# TeensyPedal.net
KiCad netlist of a schematic drawn in EAGLE
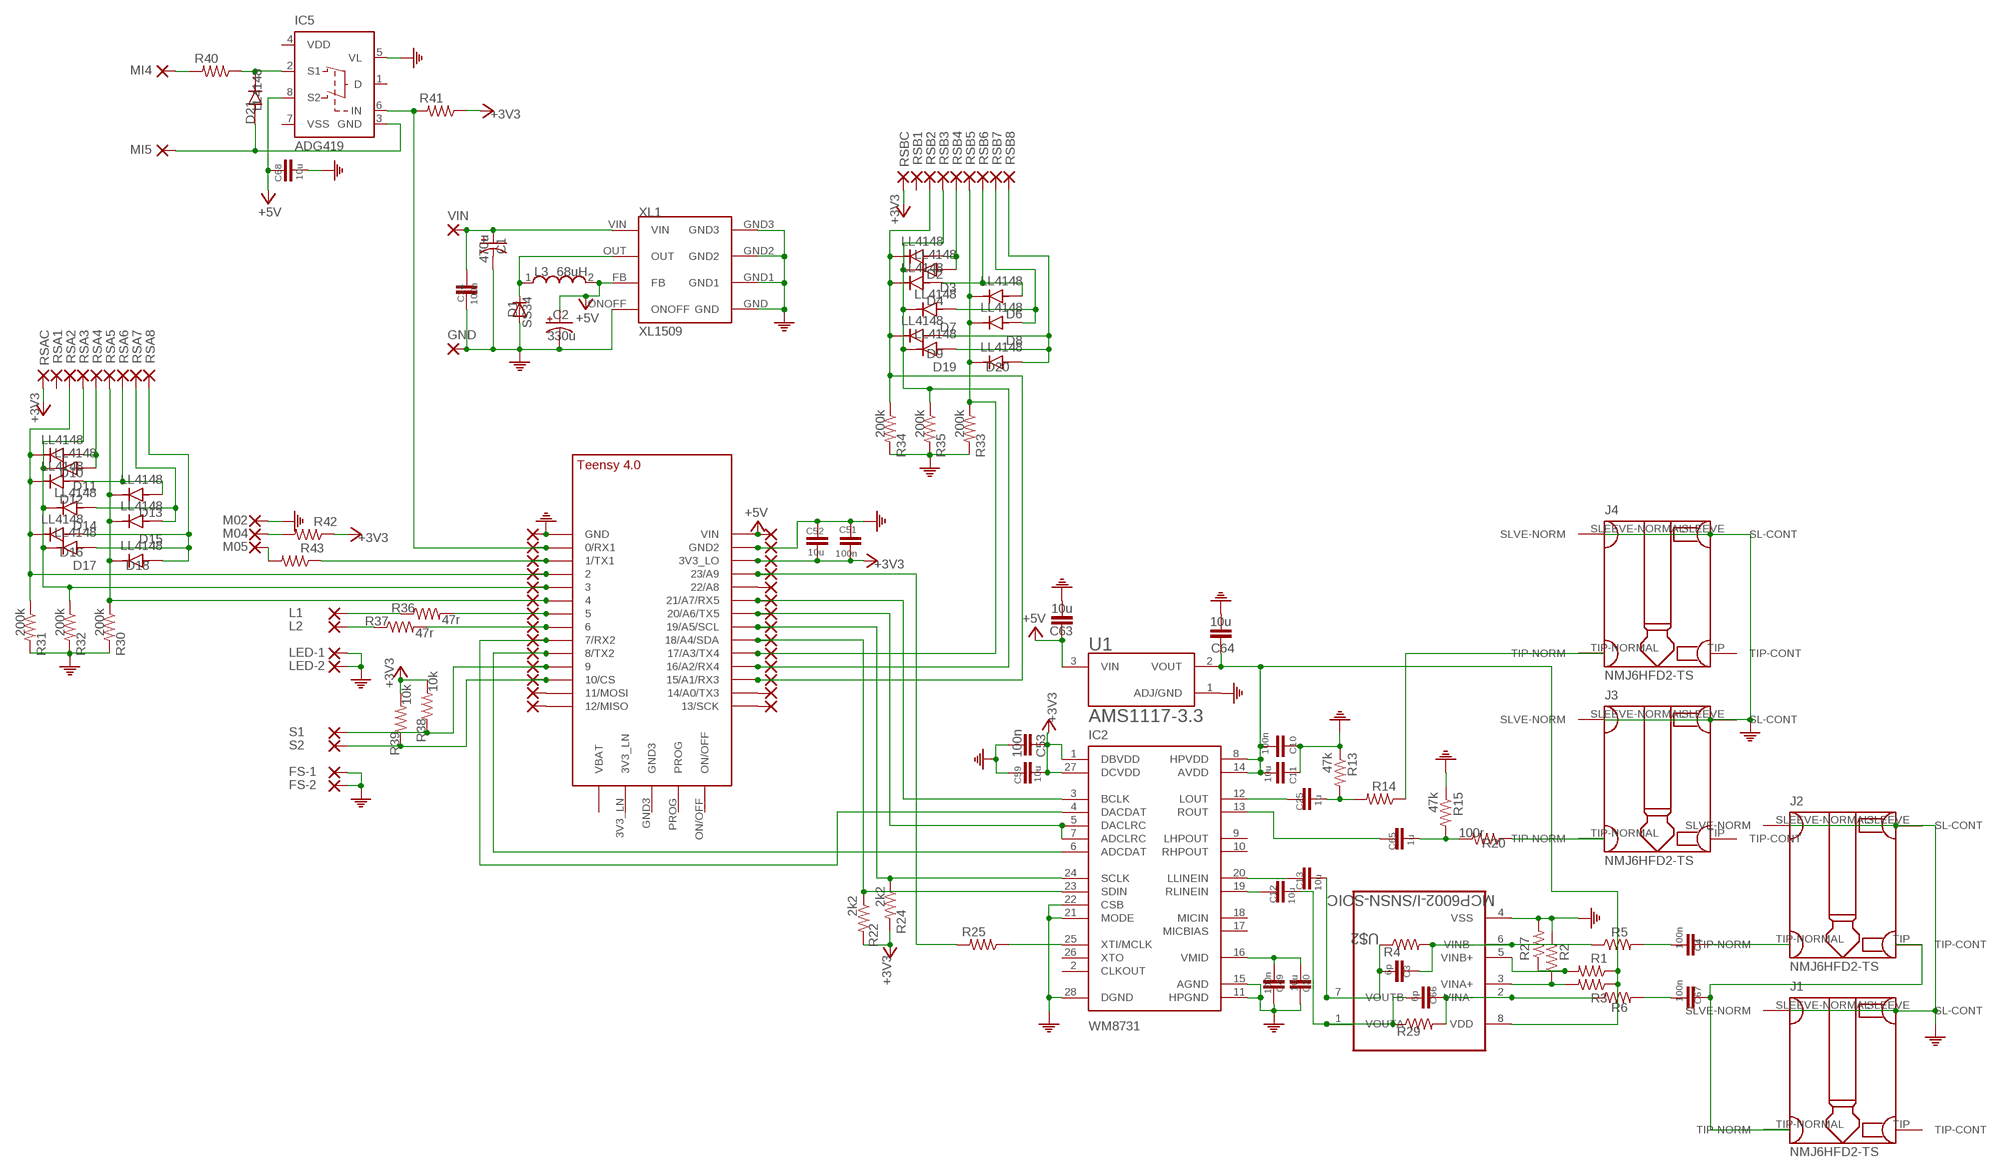
[diagram p0: schematic, sheet 1]

(export (version "E")
  (design (tool "Eeschema 10.0.6"))
  (components
    (comp (ref "+5V")
      (value "1,6/0,9")
      (footprint "eagle-import:1,6_0,9")
      (libsource (lib "eagle-import") (part "1,6/0,9"))
    )
    (comp (ref "C1")
      (value "470u")
      (footprint "eagle-import:B45181B")
      (libsource (lib "eagle-import") (part "CPOL-USB45181B"))
    )
    (comp (ref "C2")
      (value "330u")
      (footprint "eagle-import:B45181B")
      (libsource (lib "eagle-import") (part "CPOL-USB45181B"))
    )
    (comp (ref "C3")
      (value "6p")
      (footprint "eagle-import:C0603")
      (libsource (lib "eagle-import") (part "C-EUC0603"))
    )
    (comp (ref "C4")
      (value "100n")
      (footprint "eagle-import:C0603")
      (libsource (lib "eagle-import") (part "C-EUC0603"))
    )
    (comp (ref "C10")
      (value "100n")
      (footprint "eagle-import:C0603")
      (libsource (lib "eagle-import") (part "C-EUC0603"))
    )
    (comp (ref "C11")
      (value "10u")
      (footprint "eagle-import:C0805")
      (libsource (lib "eagle-import") (part "C-EUC0805"))
    )
    (comp (ref "C12")
      (value "10u")
      (footprint "eagle-import:C0805")
      (libsource (lib "eagle-import") (part "C-EUC0805"))
    )
    (comp (ref "C13")
      (value "10u")
      (footprint "eagle-import:C0805")
      (libsource (lib "eagle-import") (part "C-EUC0805"))
    )
    (comp (ref "C14")
      (value "100n")
      (footprint "eagle-import:C0603")
      (libsource (lib "eagle-import") (part "C-EUC0603"))
    )
    (comp (ref "C25")
      (value "1u")
      (footprint "eagle-import:C0603")
      (libsource (lib "eagle-import") (part "C-EUC0603"))
    )
    (comp (ref "C30")
      (value "10u")
      (footprint "eagle-import:C0805")
      (libsource (lib "eagle-import") (part "C-EUC0805"))
    )
    (comp (ref "C49")
      (value "100n")
      (footprint "eagle-import:C0603")
      (libsource (lib "eagle-import") (part "C-EUC0603"))
    )
    (comp (ref "C51")
      (value "100n")
      (footprint "eagle-import:C0603")
      (libsource (lib "eagle-import") (part "C-EUC0603"))
    )
    (comp (ref "C52")
      (value "10u")
      (footprint "eagle-import:C0805")
      (libsource (lib "eagle-import") (part "C-EUC0805"))
    )
    (comp (ref "C53")
      (value "100n")
      (footprint "eagle-import:C0603")
      (libsource (lib "eagle-import") (part "C-EUC0603"))
    )
    (comp (ref "C59")
      (value "10u")
      (footprint "eagle-import:C0805")
      (libsource (lib "eagle-import") (part "C-EUC0805"))
    )
    (comp (ref "C63")
      (value "10u")
      (footprint "eagle-import:C0805")
      (libsource (lib "eagle-import") (part "C-EUC0805"))
    )
    (comp (ref "C64")
      (value "10u")
      (footprint "eagle-import:C0805")
      (libsource (lib "eagle-import") (part "C-EUC0805"))
    )
    (comp (ref "C65")
      (value "1u")
      (footprint "eagle-import:C0603")
      (libsource (lib "eagle-import") (part "C-EUC0603"))
    )
    (comp (ref "C66")
      (value "6p")
      (footprint "eagle-import:C0603")
      (libsource (lib "eagle-import") (part "C-EUC0603"))
    )
    (comp (ref "C67")
      (value "100n")
      (footprint "eagle-import:C0603")
      (libsource (lib "eagle-import") (part "C-EUC0603"))
    )
    (comp (ref "C68")
      (value "10u")
      (footprint "eagle-import:C0805")
      (libsource (lib "eagle-import") (part "C-EUC0805"))
    )
    (comp (ref "D1")
      (value "SS34")
      (footprint "eagle-import:DO214AC")
      (libsource (lib "eagle-import") (part "DIODE-DO214AC"))
    )
    (comp (ref "D2")
      (value "LL4148")
      (footprint "eagle-import:DIO_LL4148")
      (fields (field (name "MF") "ON Semiconductor"))
      (libsource (lib "eagle-import") (part "LL4148"))
    )
    (comp (ref "D3")
      (value "LL4148")
      (footprint "eagle-import:DIO_LL4148")
      (fields (field (name "MF") "ON Semiconductor"))
      (libsource (lib "eagle-import") (part "LL4148"))
    )
    (comp (ref "D4")
      (value "LL4148")
      (footprint "eagle-import:DIO_LL4148")
      (fields (field (name "MF") "ON Semiconductor"))
      (libsource (lib "eagle-import") (part "LL4148"))
    )
    (comp (ref "D6")
      (value "LL4148")
      (footprint "eagle-import:DIO_LL4148")
      (fields (field (name "MF") "ON Semiconductor"))
      (libsource (lib "eagle-import") (part "LL4148"))
    )
    (comp (ref "D7")
      (value "LL4148")
      (footprint "eagle-import:DIO_LL4148")
      (fields (field (name "MF") "ON Semiconductor"))
      (libsource (lib "eagle-import") (part "LL4148"))
    )
    (comp (ref "D8")
      (value "LL4148")
      (footprint "eagle-import:DIO_LL4148")
      (fields (field (name "MF") "ON Semiconductor"))
      (libsource (lib "eagle-import") (part "LL4148"))
    )
    (comp (ref "D9")
      (value "LL4148")
      (footprint "eagle-import:DIO_LL4148")
      (fields (field (name "MF") "ON Semiconductor"))
      (libsource (lib "eagle-import") (part "LL4148"))
    )
    (comp (ref "D10")
      (value "LL4148")
      (footprint "eagle-import:DIO_LL4148")
      (fields (field (name "MF") "ON Semiconductor"))
      (libsource (lib "eagle-import") (part "LL4148"))
    )
    (comp (ref "D11")
      (value "LL4148")
      (footprint "eagle-import:DIO_LL4148")
      (fields (field (name "MF") "ON Semiconductor"))
      (libsource (lib "eagle-import") (part "LL4148"))
    )
    (comp (ref "D12")
      (value "LL4148")
      (footprint "eagle-import:DIO_LL4148")
      (fields (field (name "MF") "ON Semiconductor"))
      (libsource (lib "eagle-import") (part "LL4148"))
    )
    (comp (ref "D13")
      (value "LL4148")
      (footprint "eagle-import:DIO_LL4148")
      (fields (field (name "MF") "ON Semiconductor"))
      (libsource (lib "eagle-import") (part "LL4148"))
    )
    (comp (ref "D14")
      (value "LL4148")
      (footprint "eagle-import:DIO_LL4148")
      (fields (field (name "MF") "ON Semiconductor"))
      (libsource (lib "eagle-import") (part "LL4148"))
    )
    (comp (ref "D15")
      (value "LL4148")
      (footprint "eagle-import:DIO_LL4148")
      (fields (field (name "MF") "ON Semiconductor"))
      (libsource (lib "eagle-import") (part "LL4148"))
    )
    (comp (ref "D16")
      (value "LL4148")
      (footprint "eagle-import:DIO_LL4148")
      (fields (field (name "MF") "ON Semiconductor"))
      (libsource (lib "eagle-import") (part "LL4148"))
    )
    (comp (ref "D17")
      (value "LL4148")
      (footprint "eagle-import:DIO_LL4148")
      (fields (field (name "MF") "ON Semiconductor"))
      (libsource (lib "eagle-import") (part "LL4148"))
    )
    (comp (ref "D18")
      (value "LL4148")
      (footprint "eagle-import:DIO_LL4148")
      (fields (field (name "MF") "ON Semiconductor"))
      (libsource (lib "eagle-import") (part "LL4148"))
    )
    (comp (ref "D19")
      (value "LL4148")
      (footprint "eagle-import:DIO_LL4148")
      (fields (field (name "MF") "ON Semiconductor"))
      (libsource (lib "eagle-import") (part "LL4148"))
    )
    (comp (ref "D20")
      (value "LL4148")
      (footprint "eagle-import:DIO_LL4148")
      (fields (field (name "MF") "ON Semiconductor"))
      (libsource (lib "eagle-import") (part "LL4148"))
    )
    (comp (ref "D21")
      (value "LL4148")
      (footprint "eagle-import:DIO_LL4148")
      (fields (field (name "MF") "ON Semiconductor"))
      (libsource (lib "eagle-import") (part "LL4148"))
    )
    (comp (ref "FS-1")
      (value "1,6/0,9")
      (footprint "eagle-import:1,6_0,9")
      (libsource (lib "eagle-import") (part "1,6/0,9"))
    )
    (comp (ref "FS-2")
      (value "1,6/0,9")
      (footprint "eagle-import:1,6_0,9")
      (libsource (lib "eagle-import") (part "1,6/0,9"))
    )
    (comp (ref "GND")
      (value "1,6/0,9")
      (footprint "eagle-import:1,6_0,9")
      (libsource (lib "eagle-import") (part "1,6/0,9"))
    )
    (comp (ref "GND10")
      (value "2,15/1,0")
      (footprint "eagle-import:2,15_1,0")
      (libsource (lib "eagle-import") (part "2,15/1,0"))
    )
    (comp (ref "IC2")
      (value "WM8731")
      (footprint "eagle-import:SSOP28")
      (libsource (lib "eagle-import") (part "WM8731"))
    )
    (comp (ref "IC5")
      (value "ADG419")
      (footprint "eagle-import:DIL08")
      (fields (field (name "MF") "ALTERA CORPORATION") (field (name "MPN") "ADG419BN"))
      (libsource (lib "eagle-import") (part "ADG419"))
    )
    (comp (ref "J1")
      (value "NMJ6HFD2-TS")
      (footprint "eagle-import:NMJ6HFD2-TS")
      (libsource (lib "eagle-import") (part "NMJ6HFD2-TS"))
    )
    (comp (ref "J2")
      (value "NMJ6HFD2-TS")
      (footprint "eagle-import:NMJ6HFD2-TS")
      (libsource (lib "eagle-import") (part "NMJ6HFD2-TS"))
    )
    (comp (ref "J3")
      (value "NMJ6HFD2-TS")
      (footprint "eagle-import:NMJ6HFD2-TS")
      (libsource (lib "eagle-import") (part "NMJ6HFD2-TS"))
    )
    (comp (ref "J4")
      (value "NMJ6HFD2-TS")
      (footprint "eagle-import:NMJ6HFD2-TS")
      (libsource (lib "eagle-import") (part "NMJ6HFD2-TS"))
    )
    (comp (ref "L1")
      (value "1,6/0,9")
      (footprint "eagle-import:1,6_0,9")
      (libsource (lib "eagle-import") (part "1,6/0,9"))
    )
    (comp (ref "L2")
      (value "1,6/0,9")
      (footprint "eagle-import:1,6_0,9")
      (libsource (lib "eagle-import") (part "1,6/0,9"))
    )
    (comp (ref "L3")
      (value "68uH")
      (footprint "eagle-import:WE-PD_1260_1245_1280_1210")
      (libsource (lib "eagle-import") (part "WE-PD_1260/1245/1280/1210"))
    )
    (comp (ref "LED-1")
      (value "1,6/0,9")
      (footprint "eagle-import:1,6_0,9")
      (libsource (lib "eagle-import") (part "1,6/0,9"))
    )
    (comp (ref "LED-2")
      (value "1,6/0,9")
      (footprint "eagle-import:1,6_0,9")
      (libsource (lib "eagle-import") (part "1,6/0,9"))
    )
    (comp (ref "M02")
      (value "2,15/1,0")
      (footprint "eagle-import:2,15_1,0")
      (libsource (lib "eagle-import") (part "2,15/1,0"))
    )
    (comp (ref "M04")
      (value "2,15/1,0")
      (footprint "eagle-import:2,15_1,0")
      (libsource (lib "eagle-import") (part "2,15/1,0"))
    )
    (comp (ref "M05")
      (value "2,15/1,0")
      (footprint "eagle-import:2,15_1,0")
      (libsource (lib "eagle-import") (part "2,15/1,0"))
    )
    (comp (ref "MI4")
      (value "2,15/1,0")
      (footprint "eagle-import:2,15_1,0")
      (libsource (lib "eagle-import") (part "2,15/1,0"))
    )
    (comp (ref "MI5")
      (value "2,15/1,0")
      (footprint "eagle-import:2,15_1,0")
      (libsource (lib "eagle-import") (part "2,15/1,0"))
    )
    (comp (ref "PIN")
      (value "1,6/0,9")
      (footprint "eagle-import:1,6_0,9")
      (libsource (lib "eagle-import") (part "1,6/0,9"))
    )
    (comp (ref "PIN1")
      (value "1,6/0,9")
      (footprint "eagle-import:1,6_0,9")
      (libsource (lib "eagle-import") (part "1,6/0,9"))
    )
    (comp (ref "PIN2")
      (value "1,6/0,9")
      (footprint "eagle-import:1,6_0,9")
      (libsource (lib "eagle-import") (part "1,6/0,9"))
    )
    (comp (ref "PIN3")
      (value "1,6/0,9")
      (footprint "eagle-import:1,6_0,9")
      (libsource (lib "eagle-import") (part "1,6/0,9"))
    )
    (comp (ref "PIN4")
      (value "1,6/0,9")
      (footprint "eagle-import:1,6_0,9")
      (libsource (lib "eagle-import") (part "1,6/0,9"))
    )
    (comp (ref "PIN5")
      (value "1,6/0,9")
      (footprint "eagle-import:1,6_0,9")
      (libsource (lib "eagle-import") (part "1,6/0,9"))
    )
    (comp (ref "PIN6")
      (value "1,6/0,9")
      (footprint "eagle-import:1,6_0,9")
      (libsource (lib "eagle-import") (part "1,6/0,9"))
    )
    (comp (ref "PIN7")
      (value "1,6/0,9")
      (footprint "eagle-import:1,6_0,9")
      (libsource (lib "eagle-import") (part "1,6/0,9"))
    )
    (comp (ref "PIN8")
      (value "1,6/0,9")
      (footprint "eagle-import:1,6_0,9")
      (libsource (lib "eagle-import") (part "1,6/0,9"))
    )
    (comp (ref "PIN9")
      (value "1,6/0,9")
      (footprint "eagle-import:1,6_0,9")
      (libsource (lib "eagle-import") (part "1,6/0,9"))
    )
    (comp (ref "PIN10")
      (value "1,6/0,9")
      (footprint "eagle-import:1,6_0,9")
      (libsource (lib "eagle-import") (part "1,6/0,9"))
    )
    (comp (ref "PIN11")
      (value "1,6/0,9")
      (footprint "eagle-import:1,6_0,9")
      (libsource (lib "eagle-import") (part "1,6/0,9"))
    )
    (comp (ref "PIN12")
      (value "1,6/0,9")
      (footprint "eagle-import:1,6_0,9")
      (libsource (lib "eagle-import") (part "1,6/0,9"))
    )
    (comp (ref "PIN13")
      (value "1,6/0,9")
      (footprint "eagle-import:1,6_0,9")
      (libsource (lib "eagle-import") (part "1,6/0,9"))
    )
    (comp (ref "PIN14")
      (value "1,6/0,9")
      (footprint "eagle-import:1,6_0,9")
      (libsource (lib "eagle-import") (part "1,6/0,9"))
    )
    (comp (ref "PIN15")
      (value "1,6/0,9")
      (footprint "eagle-import:1,6_0,9")
      (libsource (lib "eagle-import") (part "1,6/0,9"))
    )
    (comp (ref "PIN16")
      (value "1,6/0,9")
      (footprint "eagle-import:1,6_0,9")
      (libsource (lib "eagle-import") (part "1,6/0,9"))
    )
    (comp (ref "PIN17")
      (value "1,6/0,9")
      (footprint "eagle-import:1,6_0,9")
      (libsource (lib "eagle-import") (part "1,6/0,9"))
    )
    (comp (ref "PIN18")
      (value "1,6/0,9")
      (footprint "eagle-import:1,6_0,9")
      (libsource (lib "eagle-import") (part "1,6/0,9"))
    )
    (comp (ref "PIN19")
      (value "1,6/0,9")
      (footprint "eagle-import:1,6_0,9")
      (libsource (lib "eagle-import") (part "1,6/0,9"))
    )
    (comp (ref "PIN20")
      (value "1,6/0,9")
      (footprint "eagle-import:1,6_0,9")
      (libsource (lib "eagle-import") (part "1,6/0,9"))
    )
    (comp (ref "PIN21")
      (value "1,6/0,9")
      (footprint "eagle-import:1,6_0,9")
      (libsource (lib "eagle-import") (part "1,6/0,9"))
    )
    (comp (ref "PIN22")
      (value "1,6/0,9")
      (footprint "eagle-import:1,6_0,9")
      (libsource (lib "eagle-import") (part "1,6/0,9"))
    )
    (comp (ref "PIN23")
      (value "1,6/0,9")
      (footprint "eagle-import:1,6_0,9")
      (libsource (lib "eagle-import") (part "1,6/0,9"))
    )
    (comp (ref "PIN24")
      (value "1,6/0,9")
      (footprint "eagle-import:1,6_0,9")
      (libsource (lib "eagle-import") (part "1,6/0,9"))
    )
    (comp (ref "PIN25")
      (value "1,6/0,9")
      (footprint "eagle-import:1,6_0,9")
      (libsource (lib "eagle-import") (part "1,6/0,9"))
    )
    (comp (ref "R1")
      (value "200k")
      (footprint "eagle-import:R0603")
      (libsource (lib "eagle-import") (part "R-US_R0603"))
    )
    (comp (ref "R2")
      (value "200k")
      (footprint "eagle-import:R0603")
      (libsource (lib "eagle-import") (part "R-US_R0603"))
    )
    (comp (ref "R3")
      (value "200k")
      (footprint "eagle-import:R0603")
      (libsource (lib "eagle-import") (part "R-US_R0603"))
    )
    (comp (ref "R4")
      (value "1m")
      (footprint "eagle-import:0204_7")
      (libsource (lib "eagle-import") (part "R-US_0204/7"))
    )
    (comp (ref "R5")
      (value "1m")
      (footprint "eagle-import:R0603")
      (libsource (lib "eagle-import") (part "R-US_R0603"))
    )
    (comp (ref "R6")
      (value "1m")
      (footprint "eagle-import:R0603")
      (libsource (lib "eagle-import") (part "R-US_R0603"))
    )
    (comp (ref "R13")
      (value "47k")
      (footprint "eagle-import:R0603")
      (libsource (lib "eagle-import") (part "R-US_R0603"))
    )
    (comp (ref "R14")
      (value "100r")
      (footprint "eagle-import:R0603")
      (libsource (lib "eagle-import") (part "R-US_R0603"))
    )
    (comp (ref "R15")
      (value "47k")
      (footprint "eagle-import:R0603")
      (libsource (lib "eagle-import") (part "R-US_R0603"))
    )
    (comp (ref "R20")
      (value "100r")
      (footprint "eagle-import:R0603")
      (libsource (lib "eagle-import") (part "R-US_R0603"))
    )
    (comp (ref "R22")
      (value "2k2")
      (footprint "eagle-import:R0603")
      (libsource (lib "eagle-import") (part "R-US_R0603"))
    )
    (comp (ref "R24")
      (value "2k2")
      (footprint "eagle-import:R0603")
      (libsource (lib "eagle-import") (part "R-US_R0603"))
    )
    (comp (ref "R25")
      (value "220r")
      (footprint "eagle-import:R0603")
      (libsource (lib "eagle-import") (part "R-US_R0603"))
    )
    (comp (ref "R27")
      (value "200k")
      (footprint "eagle-import:R0603")
      (libsource (lib "eagle-import") (part "R-US_R0603"))
    )
    (comp (ref "R29")
      (value "1m")
      (footprint "eagle-import:0204_7")
      (libsource (lib "eagle-import") (part "R-US_0204/7"))
    )
    (comp (ref "R30")
      (value "200k")
      (footprint "eagle-import:R0603")
      (libsource (lib "eagle-import") (part "R-US_R0603"))
    )
    (comp (ref "R31")
      (value "200k")
      (footprint "eagle-import:R0603")
      (libsource (lib "eagle-import") (part "R-US_R0603"))
    )
    (comp (ref "R32")
      (value "200k")
      (footprint "eagle-import:R0603")
      (libsource (lib "eagle-import") (part "R-US_R0603"))
    )
    (comp (ref "R33")
      (value "200k")
      (footprint "eagle-import:R0603")
      (libsource (lib "eagle-import") (part "R-US_R0603"))
    )
    (comp (ref "R34")
      (value "200k")
      (footprint "eagle-import:R0603")
      (libsource (lib "eagle-import") (part "R-US_R0603"))
    )
    (comp (ref "R35")
      (value "200k")
      (footprint "eagle-import:R0603")
      (libsource (lib "eagle-import") (part "R-US_R0603"))
    )
    (comp (ref "R36")
      (value "47r")
      (footprint "eagle-import:R0603")
      (libsource (lib "eagle-import") (part "R-US_R0603"))
    )
    (comp (ref "R37")
      (value "47r")
      (footprint "eagle-import:R0603")
      (libsource (lib "eagle-import") (part "R-US_R0603"))
    )
    (comp (ref "R38")
      (value "10k")
      (footprint "eagle-import:R0603")
      (libsource (lib "eagle-import") (part "R-US_R0603"))
    )
    (comp (ref "R39")
      (value "10k")
      (footprint "eagle-import:R0603")
      (libsource (lib "eagle-import") (part "R-US_R0603"))
    )
    (comp (ref "R40")
      (value "220r")
      (footprint "eagle-import:R0603")
      (libsource (lib "eagle-import") (part "R-US_R0603"))
    )
    (comp (ref "R41")
      (value "470r")
      (footprint "eagle-import:R0603")
      (libsource (lib "eagle-import") (part "R-US_R0603"))
    )
    (comp (ref "R42")
      (value "47r")
      (footprint "eagle-import:R0603")
      (libsource (lib "eagle-import") (part "R-US_R0603"))
    )
    (comp (ref "R43")
      (value "47r")
      (footprint "eagle-import:R0603")
      (libsource (lib "eagle-import") (part "R-US_R0603"))
    )
    (comp (ref "RSA1")
      (value "2,15/1,0")
      (footprint "eagle-import:2,15_1,0")
      (libsource (lib "eagle-import") (part "2,15/1,0"))
    )
    (comp (ref "RSA2")
      (value "2,15/1,0")
      (footprint "eagle-import:2,15_1,0")
      (libsource (lib "eagle-import") (part "2,15/1,0"))
    )
    (comp (ref "RSA3")
      (value "2,15/1,0")
      (footprint "eagle-import:2,15_1,0")
      (libsource (lib "eagle-import") (part "2,15/1,0"))
    )
    (comp (ref "RSA4")
      (value "2,15/1,0")
      (footprint "eagle-import:2,15_1,0")
      (libsource (lib "eagle-import") (part "2,15/1,0"))
    )
    (comp (ref "RSA5")
      (value "2,15/1,0")
      (footprint "eagle-import:2,15_1,0")
      (libsource (lib "eagle-import") (part "2,15/1,0"))
    )
    (comp (ref "RSA6")
      (value "2,15/1,0")
      (footprint "eagle-import:2,15_1,0")
      (libsource (lib "eagle-import") (part "2,15/1,0"))
    )
    (comp (ref "RSA7")
      (value "2,15/1,0")
      (footprint "eagle-import:2,15_1,0")
      (libsource (lib "eagle-import") (part "2,15/1,0"))
    )
    (comp (ref "RSA8")
      (value "2,15/1,0")
      (footprint "eagle-import:2,15_1,0")
      (libsource (lib "eagle-import") (part "2,15/1,0"))
    )
    (comp (ref "RSAC")
      (value "2,15/1,0")
      (footprint "eagle-import:2,15_1,0")
      (libsource (lib "eagle-import") (part "2,15/1,0"))
    )
    (comp (ref "RSB1")
      (value "2,54/1,1")
      (footprint "eagle-import:2,54_1,1")
      (libsource (lib "eagle-import") (part "2,54/1,1"))
    )
    (comp (ref "RSB2")
      (value "2,15/1,0")
      (footprint "eagle-import:2,15_1,0")
      (libsource (lib "eagle-import") (part "2,15/1,0"))
    )
    (comp (ref "RSB3")
      (value "2,15/1,0")
      (footprint "eagle-import:2,15_1,0")
      (libsource (lib "eagle-import") (part "2,15/1,0"))
    )
    (comp (ref "RSB4")
      (value "2,15/1,0")
      (footprint "eagle-import:2,15_1,0")
      (libsource (lib "eagle-import") (part "2,15/1,0"))
    )
    (comp (ref "RSB5")
      (value "2,15/1,0")
      (footprint "eagle-import:2,15_1,0")
      (libsource (lib "eagle-import") (part "2,15/1,0"))
    )
    (comp (ref "RSB6")
      (value "2,15/1,0")
      (footprint "eagle-import:2,15_1,0")
      (libsource (lib "eagle-import") (part "2,15/1,0"))
    )
    (comp (ref "RSB7")
      (value "2,15/1,0")
      (footprint "eagle-import:2,15_1,0")
      (libsource (lib "eagle-import") (part "2,15/1,0"))
    )
    (comp (ref "RSB8")
      (value "2,15/1,0")
      (footprint "eagle-import:2,15_1,0")
      (libsource (lib "eagle-import") (part "2,15/1,0"))
    )
    (comp (ref "RSBC")
      (value "2,15/1,0")
      (footprint "eagle-import:2,15_1,0")
      (libsource (lib "eagle-import") (part "2,15/1,0"))
    )
    (comp (ref "S1")
      (value "1,6/0,9")
      (footprint "eagle-import:1,6_0,9")
      (libsource (lib "eagle-import") (part "1,6/0,9"))
    )
    (comp (ref "S2")
      (value "1,6/0,9")
      (footprint "eagle-import:1,6_0,9")
      (libsource (lib "eagle-import") (part "1,6/0,9"))
    )
    (comp (ref "U$1")
      (value "TEENSY_4.0")
      (footprint "eagle-import:TEENSY_4.0")
      (libsource (lib "eagle-import") (part "TEENSY_4.0"))
    )
    (comp (ref "U$2")
      (value "MCP6002-I/SNSN-SOIC")
      (footprint "eagle-import:SOIC127P690X150-8N")
      (libsource (lib "eagle-import") (part "MCP6002-I/SNSN-SOIC"))
    )
    (comp (ref "U1")
      (value "AMS1117-3.3")
      (footprint "eagle-import:SOT229P700X180-4N")
      (fields (field (name "MF") "Advanced Monolithic Systems"))
      (libsource (lib "eagle-import") (part "AMS1117-3.3"))
    )
    (comp (ref "VIN")
      (value "2,15/1,0")
      (footprint "eagle-import:2,15_1,0")
      (libsource (lib "eagle-import") (part "2,15/1,0"))
    )
    (comp (ref "XL1")
      (value "XL1509")
      (footprint "eagle-import:XL1509")
      (libsource (lib "eagle-import") (part "XL1509"))
    )
  )
  (nets
    (net (code "1") (name "+3V3") (class "Default")
      (node (ref "C51") (pin "1") (pinfunction "1_1") (pintype "passive"))
      (node (ref "C52") (pin "2") (pinfunction "2_2") (pintype "passive"))
      (node (ref "C53") (pin "1") (pinfunction "1_1") (pintype "passive"))
      (node (ref "C59") (pin "2") (pinfunction "2_2") (pintype "passive"))
      (node (ref "IC2") (pin "1") (pinfunction "DBVDD_1") (pintype "bidirectional"))
      (node (ref "IC2") (pin "27") (pinfunction "DCVDD_27") (pintype "bidirectional"))
      (node (ref "PIN24") (pin "1") (pinfunction "P_1") (pintype "passive"))
      (node (ref "R22") (pin "2") (pinfunction "2_2") (pintype "passive"))
      (node (ref "R24") (pin "2") (pinfunction "2_2") (pintype "passive"))
      (node (ref "R38") (pin "2") (pinfunction "2_2") (pintype "passive"))
      (node (ref "R39") (pin "2") (pinfunction "2_2") (pintype "passive"))
      (node (ref "R41") (pin "1") (pinfunction "1_1") (pintype "passive"))
      (node (ref "R42") (pin "1") (pinfunction "1_1") (pintype "passive"))
      (node (ref "RSAC") (pin "1") (pinfunction "P_1") (pintype "passive"))
      (node (ref "RSBC") (pin "1") (pinfunction "P_1") (pintype "passive"))
      (node (ref "U$1") (pin "3V3_LO") (pinfunction "3V3_LO_3V3_LO") (pintype "bidirectional"))
    )
    (net (code "2") (name "+5V") (class "Default")
      (node (ref "+5V") (pin "1") (pinfunction "P_1") (pintype "passive"))
      (node (ref "C2") (pin "+") (pinfunction "+_+") (pintype "passive"))
      (node (ref "C63") (pin "1") (pinfunction "1_1") (pintype "passive"))
      (node (ref "C68") (pin "1") (pinfunction "1_1") (pintype "passive"))
      (node (ref "IC5") (pin "8") (pinfunction "S2_8") (pintype "bidirectional"))
      (node (ref "L3") (pin "2") (pinfunction "2_2") (pintype "passive"))
      (node (ref "U$1") (pin "VIN") (pinfunction "VIN_VIN") (pintype "bidirectional"))
      (node (ref "U1") (pin "3") (pinfunction "VIN_3") (pintype "input"))
      (node (ref "XL1") (pin "FB") (pinfunction "FB_FB") (pintype "bidirectional"))
    )
    (net (code "3") (name "/VDD") (class "Default")
      (node (ref "IC5") (pin "4") (pinfunction "VDD_4") (pintype "power_in"))
    )
    (net (code "4") (name "/VSS") (class "Default")
      (node (ref "IC5") (pin "7") (pinfunction "VSS_7") (pintype "power_in"))
    )
    (net (code "5") (name "Net-(C4-Pad1)") (class "Default")
      (node (ref "C4") (pin "1") (pinfunction "1_1") (pintype "passive"))
      (node (ref "R5") (pin "2") (pinfunction "2_2") (pintype "passive"))
    )
    (net (code "6") (name "Net-(C25-Pad1)") (class "Default")
      (node (ref "C25") (pin "1") (pinfunction "1_1") (pintype "passive"))
      (node (ref "R13") (pin "2") (pinfunction "2_2") (pintype "passive"))
      (node (ref "R14") (pin "2") (pinfunction "2_2") (pintype "passive"))
    )
    (net (code "7") (name "Net-(C65-Pad1)") (class "Default")
      (node (ref "C65") (pin "1") (pinfunction "1_1") (pintype "passive"))
      (node (ref "R15") (pin "2") (pinfunction "2_2") (pintype "passive"))
      (node (ref "R20") (pin "2") (pinfunction "2_2") (pintype "passive"))
    )
    (net (code "8") (name "Net-(C67-Pad1)") (class "Default")
      (node (ref "C67") (pin "1") (pinfunction "1_1") (pintype "passive"))
      (node (ref "R6") (pin "2") (pinfunction "2_2") (pintype "passive"))
    )
    (net (code "9") (name "Net-(D1-PadC)") (class "Default")
      (node (ref "D1") (pin "C") (pinfunction "C_C") (pintype "passive"))
      (node (ref "L3") (pin "1") (pinfunction "1_1") (pintype "passive"))
      (node (ref "XL1") (pin "OUT") (pinfunction "OUT_OUT") (pintype "bidirectional"))
    )
    (net (code "10") (name "Net-(IC2-ADCDAT)") (class "Default")
      (node (ref "IC2") (pin "6") (pinfunction "ADCDAT_6") (pintype "bidirectional"))
      (node (ref "PIN8") (pin "1") (pinfunction "P_1") (pintype "passive"))
      (node (ref "U$1") (pin "8") (pinfunction "8/TX2_8") (pintype "bidirectional"))
    )
    (net (code "11") (name "Net-(IC2-ADCLRC)") (class "Default")
      (node (ref "IC2") (pin "5") (pinfunction "DACLRC_5") (pintype "bidirectional"))
      (node (ref "IC2") (pin "7") (pinfunction "ADCLRC_7") (pintype "bidirectional"))
      (node (ref "PIN20") (pin "1") (pinfunction "P_1") (pintype "passive"))
      (node (ref "U$1") (pin "20/A6") (pinfunction "20/A6/TX5_20/A6") (pintype "bidirectional"))
    )
    (net (code "12") (name "Net-(IC2-AVDD)") (class "Default")
      (node (ref "C10") (pin "1") (pinfunction "1_1") (pintype "passive"))
      (node (ref "C11") (pin "1") (pinfunction "1_1") (pintype "passive"))
      (node (ref "C64") (pin "1") (pinfunction "1_1") (pintype "passive"))
      (node (ref "IC2") (pin "14") (pinfunction "AVDD_14") (pintype "bidirectional"))
      (node (ref "IC2") (pin "8") (pinfunction "HPVDD_8") (pintype "bidirectional"))
      (node (ref "R1") (pin "1") (pinfunction "1_1") (pintype "passive"))
      (node (ref "R3") (pin "1") (pinfunction "1_1") (pintype "passive"))
      (node (ref "U$2") (pin "8") (pinfunction "VDD_8") (pintype "power_in"))
      (node (ref "U1") (pin "2") (pinfunction "VOUT_2") (pintype "output"))
    )
    (net (code "13") (name "Net-(IC2-BCLK)") (class "Default")
      (node (ref "IC2") (pin "3") (pinfunction "BCLK_3") (pintype "bidirectional"))
      (node (ref "PIN21") (pin "1") (pinfunction "P_1") (pintype "passive"))
      (node (ref "U$1") (pin "21/A7") (pinfunction "21/A7/RX5_21/A7") (pintype "bidirectional"))
    )
    (net (code "14") (name "Net-(IC2-DACDAT)") (class "Default")
      (node (ref "IC2") (pin "4") (pinfunction "DACDAT_4") (pintype "bidirectional"))
      (node (ref "PIN7") (pin "1") (pinfunction "P_1") (pintype "passive"))
      (node (ref "U$1") (pin "7") (pinfunction "7/RX2_7") (pintype "bidirectional"))
    )
    (net (code "15") (name "Net-(IC2-LLINEIN)") (class "Default")
      (node (ref "C13") (pin "2") (pinfunction "2_2") (pintype "passive"))
      (node (ref "IC2") (pin "20") (pinfunction "LLINEIN_20") (pintype "bidirectional"))
    )
    (net (code "16") (name "Net-(IC2-LOUT)") (class "Default")
      (node (ref "C25") (pin "2") (pinfunction "2_2") (pintype "passive"))
      (node (ref "IC2") (pin "12") (pinfunction "LOUT_12") (pintype "bidirectional"))
    )
    (net (code "17") (name "Net-(IC2-RLINEIN)") (class "Default")
      (node (ref "C12") (pin "2") (pinfunction "2_2") (pintype "passive"))
      (node (ref "IC2") (pin "19") (pinfunction "RLINEIN_19") (pintype "bidirectional"))
    )
    (net (code "18") (name "Net-(IC2-ROUT)") (class "Default")
      (node (ref "C65") (pin "2") (pinfunction "2_2") (pintype "passive"))
      (node (ref "IC2") (pin "13") (pinfunction "ROUT_13") (pintype "bidirectional"))
    )
    (net (code "19") (name "Net-(IC2-SCLK)") (class "Default")
      (node (ref "IC2") (pin "24") (pinfunction "SCLK_24") (pintype "bidirectional"))
      (node (ref "PIN19") (pin "1") (pinfunction "P_1") (pintype "passive"))
      (node (ref "R24") (pin "1") (pinfunction "1_1") (pintype "passive"))
      (node (ref "U$1") (pin "19/A5/SCL") (pinfunction "19/A5/SCL_19/A5/SCL") (pintype "bidirectional"))
    )
    (net (code "20") (name "Net-(IC2-SDIN)") (class "Default")
      (node (ref "IC2") (pin "23") (pinfunction "SDIN_23") (pintype "bidirectional"))
      (node (ref "PIN18") (pin "1") (pinfunction "P_1") (pintype "passive"))
      (node (ref "R22") (pin "1") (pinfunction "1_1") (pintype "passive"))
      (node (ref "U$1") (pin "18/A4/SDA") (pinfunction "18/A4/SDA_18/A4/SDA") (pintype "bidirectional"))
    )
    (net (code "21") (name "Net-(IC2-VMID)") (class "Default")
      (node (ref "C30") (pin "2") (pinfunction "2_2") (pintype "passive"))
      (node (ref "C49") (pin "2") (pinfunction "2_2") (pintype "passive"))
      (node (ref "IC2") (pin "16") (pinfunction "VMID_16") (pintype "bidirectional"))
    )
    (net (code "22") (name "Net-(IC2-XTI{slash}MCLK)") (class "Default")
      (node (ref "IC2") (pin "25") (pinfunction "XTI/MCLK_25") (pintype "bidirectional"))
      (node (ref "R25") (pin "1") (pinfunction "1_1") (pintype "passive"))
    )
    (net (code "23") (name "Net-(IC5-GND)") (class "Default")
      (node (ref "D21") (pin "A") (pinfunction "A_A") (pintype "passive"))
      (node (ref "IC5") (pin "3") (pinfunction "GND_3") (pintype "power_in"))
      (node (ref "MI5") (pin "1") (pinfunction "P_1") (pintype "passive"))
    )
    (net (code "24") (name "Net-(IC5-IN)") (class "Default")
      (node (ref "IC5") (pin "6") (pinfunction "IN_6") (pintype "input"))
      (node (ref "PIN") (pin "1") (pinfunction "P_1") (pintype "passive"))
      (node (ref "R41") (pin "2") (pinfunction "2_2") (pintype "passive"))
      (node (ref "U$1") (pin "0/RX") (pinfunction "0/RX1_0/RX") (pintype "bidirectional"))
    )
    (net (code "25") (name "Net-(IC5-S1)") (class "Default")
      (node (ref "D21") (pin "C") (pinfunction "C_C") (pintype "passive"))
      (node (ref "IC5") (pin "2") (pinfunction "S1_2") (pintype "bidirectional"))
      (node (ref "R40") (pin "1") (pinfunction "1_1") (pintype "passive"))
    )
    (net (code "26") (name "Net-(J1-TIP-NORM)") (class "Default")
      (node (ref "C67") (pin "2") (pinfunction "2_2") (pintype "passive"))
      (node (ref "J1") (pin "TIP-NORMAL") (pinfunction "TIP-NORM_TIP-NORMAL") (pintype "bidirectional"))
      (node (ref "J2") (pin "TIP") (pinfunction "TIP-CONT_TIP") (pintype "bidirectional"))
    )
    (net (code "27") (name "Net-(J2-TIP-NORM)") (class "Default")
      (node (ref "C4") (pin "2") (pinfunction "2_2") (pintype "passive"))
      (node (ref "J2") (pin "TIP-NORMAL") (pinfunction "TIP-NORM_TIP-NORMAL") (pintype "bidirectional"))
    )
    (net (code "28") (name "Net-(J3-TIP-NORM)") (class "Default")
      (node (ref "J3") (pin "TIP-NORMAL") (pinfunction "TIP-NORM_TIP-NORMAL") (pintype "bidirectional"))
      (node (ref "R20") (pin "1") (pinfunction "1_1") (pintype "passive"))
    )
    (net (code "29") (name "Net-(J4-TIP-NORM)") (class "Default")
      (node (ref "J4") (pin "TIP-NORMAL") (pinfunction "TIP-NORM_TIP-NORMAL") (pintype "bidirectional"))
      (node (ref "R14") (pin "1") (pinfunction "1_1") (pintype "passive"))
    )
    (net (code "30") (name "Net-(L1-P)") (class "Default")
      (node (ref "L1") (pin "1") (pinfunction "P_1") (pintype "passive"))
      (node (ref "R36") (pin "1") (pinfunction "1_1") (pintype "passive"))
    )
    (net (code "31") (name "Net-(L2-P)") (class "Default")
      (node (ref "L2") (pin "1") (pinfunction "P_1") (pintype "passive"))
      (node (ref "R37") (pin "1") (pinfunction "1_1") (pintype "passive"))
    )
    (net (code "32") (name "Net-(M04-P)") (class "Default")
      (node (ref "M04") (pin "1") (pinfunction "P_1") (pintype "passive"))
      (node (ref "R42") (pin "2") (pinfunction "2_2") (pintype "passive"))
    )
    (net (code "33") (name "Net-(M05-P)") (class "Default")
      (node (ref "M05") (pin "1") (pinfunction "P_1") (pintype "passive"))
      (node (ref "R43") (pin "2") (pinfunction "2_2") (pintype "passive"))
    )
    (net (code "34") (name "Net-(MI4-P)") (class "Default")
      (node (ref "MI4") (pin "1") (pinfunction "P_1") (pintype "passive"))
      (node (ref "R40") (pin "2") (pinfunction "2_2") (pintype "passive"))
    )
    (net (code "35") (name "Net-(PIN1-P)") (class "Default")
      (node (ref "PIN1") (pin "1") (pinfunction "P_1") (pintype "passive"))
      (node (ref "R43") (pin "1") (pinfunction "1_1") (pintype "passive"))
      (node (ref "U$1") (pin "1/TX") (pinfunction "1/TX1_1/TX") (pintype "bidirectional"))
    )
    (net (code "36") (name "Net-(PIN2-P)") (class "Default")
      (node (ref "D10") (pin "C") (pinfunction "C_C") (pintype "passive"))
      (node (ref "D12") (pin "C") (pinfunction "C_C") (pintype "passive"))
      (node (ref "D16") (pin "C") (pinfunction "C_C") (pintype "passive"))
      (node (ref "PIN2") (pin "1") (pinfunction "P_1") (pintype "passive"))
      (node (ref "R31") (pin "1") (pinfunction "1_1") (pintype "passive"))
      (node (ref "RSA2") (pin "1") (pinfunction "P_1") (pintype "passive"))
      (node (ref "U$1") (pin "2") (pinfunction "2_2") (pintype "bidirectional"))
    )
    (net (code "37") (name "Net-(PIN3-P)") (class "Default")
      (node (ref "D11") (pin "C") (pinfunction "C_C") (pintype "passive"))
      (node (ref "D14") (pin "C") (pinfunction "C_C") (pintype "passive"))
      (node (ref "D17") (pin "C") (pinfunction "C_C") (pintype "passive"))
      (node (ref "PIN3") (pin "1") (pinfunction "P_1") (pintype "passive"))
      (node (ref "R32") (pin "1") (pinfunction "1_1") (pintype "passive"))
      (node (ref "RSA3") (pin "1") (pinfunction "P_1") (pintype "passive"))
      (node (ref "U$1") (pin "3/CANTX") (pinfunction "3_3/CANTX") (pintype "bidirectional"))
    )
    (net (code "38") (name "Net-(PIN4-P)") (class "Default")
      (node (ref "D13") (pin "C") (pinfunction "C_C") (pintype "passive"))
      (node (ref "D15") (pin "C") (pinfunction "C_C") (pintype "passive"))
      (node (ref "D18") (pin "C") (pinfunction "C_C") (pintype "passive"))
      (node (ref "PIN4") (pin "1") (pinfunction "P_1") (pintype "passive"))
      (node (ref "R30") (pin "1") (pinfunction "1_1") (pintype "passive"))
      (node (ref "RSA5") (pin "1") (pinfunction "P_1") (pintype "passive"))
      (node (ref "U$1") (pin "4/CANRX") (pinfunction "4_4/CANRX") (pintype "bidirectional"))
    )
    (net (code "39") (name "Net-(PIN5-P)") (class "Default")
      (node (ref "PIN5") (pin "1") (pinfunction "P_1") (pintype "passive"))
      (node (ref "R36") (pin "2") (pinfunction "2_2") (pintype "passive"))
      (node (ref "U$1") (pin "5") (pinfunction "5_5") (pintype "bidirectional"))
    )
    (net (code "40") (name "Net-(PIN6-P)") (class "Default")
      (node (ref "PIN6") (pin "1") (pinfunction "P_1") (pintype "passive"))
      (node (ref "R37") (pin "2") (pinfunction "2_2") (pintype "passive"))
      (node (ref "U$1") (pin "6") (pinfunction "6_6") (pintype "bidirectional"))
    )
    (net (code "41") (name "Net-(PIN9-P)") (class "Default")
      (node (ref "PIN9") (pin "1") (pinfunction "P_1") (pintype "passive"))
      (node (ref "R38") (pin "1") (pinfunction "1_1") (pintype "passive"))
      (node (ref "S1") (pin "1") (pinfunction "P_1") (pintype "passive"))
      (node (ref "U$1") (pin "9/CS") (pinfunction "9_9/CS") (pintype "bidirectional"))
    )
    (net (code "42") (name "Net-(PIN10-P)") (class "Default")
      (node (ref "PIN10") (pin "1") (pinfunction "P_1") (pintype "passive"))
      (node (ref "R39") (pin "1") (pinfunction "1_1") (pintype "passive"))
      (node (ref "S2") (pin "1") (pinfunction "P_1") (pintype "passive"))
      (node (ref "U$1") (pin "10/CS") (pinfunction "10/CS_10/CS") (pintype "bidirectional"))
    )
    (net (code "43") (name "Net-(PIN11-P)") (class "Default")
      (node (ref "PIN11") (pin "1") (pinfunction "P_1") (pintype "passive"))
      (node (ref "U$1") (pin "11/MOSI") (pinfunction "11/MOSI_11/MOSI") (pintype "bidirectional"))
    )
    (net (code "44") (name "Net-(PIN12-P)") (class "Default")
      (node (ref "PIN12") (pin "1") (pinfunction "P_1") (pintype "passive"))
      (node (ref "U$1") (pin "12/MISO") (pinfunction "12/MISO_12/MISO") (pintype "bidirectional"))
    )
    (net (code "45") (name "Net-(PIN13-P)") (class "Default")
      (node (ref "PIN13") (pin "1") (pinfunction "P_1") (pintype "passive"))
      (node (ref "U$1") (pin "13/SCK") (pinfunction "13/SCK_13/SCK") (pintype "bidirectional"))
    )
    (net (code "46") (name "Net-(PIN14-P)") (class "Default")
      (node (ref "PIN14") (pin "1") (pinfunction "P_1") (pintype "passive"))
      (node (ref "U$1") (pin "14/A0") (pinfunction "14/A0/TX3_14/A0") (pintype "bidirectional"))
    )
    (net (code "47") (name "Net-(PIN15-P)") (class "Default")
      (node (ref "D2") (pin "C") (pinfunction "C_C") (pintype "passive"))
      (node (ref "D4") (pin "C") (pinfunction "C_C") (pintype "passive"))
      (node (ref "D9") (pin "C") (pinfunction "C_C") (pintype "passive"))
      (node (ref "PIN15") (pin "1") (pinfunction "P_1") (pintype "passive"))
      (node (ref "R34") (pin "1") (pinfunction "1_1") (pintype "passive"))
      (node (ref "RSB2") (pin "1") (pinfunction "P_1") (pintype "passive"))
      (node (ref "U$1") (pin "15/A1") (pinfunction "15/A1/RX3_15/A1") (pintype "bidirectional"))
    )
    (net (code "48") (name "Net-(PIN16-P)") (class "Default")
      (node (ref "D19") (pin "C") (pinfunction "C_C") (pintype "passive"))
      (node (ref "D3") (pin "C") (pinfunction "C_C") (pintype "passive"))
      (node (ref "D7") (pin "C") (pinfunction "C_C") (pintype "passive"))
      (node (ref "PIN16") (pin "1") (pinfunction "P_1") (pintype "passive"))
      (node (ref "R35") (pin "1") (pinfunction "1_1") (pintype "passive"))
      (node (ref "RSB3") (pin "1") (pinfunction "P_1") (pintype "passive"))
      (node (ref "U$1") (pin "16/A2") (pinfunction "16/A2/RX4_16/A2") (pintype "bidirectional"))
    )
    (net (code "49") (name "Net-(PIN17-P)") (class "Default")
      (node (ref "D20") (pin "C") (pinfunction "C_C") (pintype "passive"))
      (node (ref "D6") (pin "C") (pinfunction "C_C") (pintype "passive"))
      (node (ref "D8") (pin "C") (pinfunction "C_C") (pintype "passive"))
      (node (ref "PIN17") (pin "1") (pinfunction "P_1") (pintype "passive"))
      (node (ref "R33") (pin "1") (pinfunction "1_1") (pintype "passive"))
      (node (ref "RSB5") (pin "1") (pinfunction "P_1") (pintype "passive"))
      (node (ref "U$1") (pin "17/A3") (pinfunction "17/A3/TX4_17/A3") (pintype "bidirectional"))
    )
    (net (code "50") (name "Net-(PIN22-P)") (class "Default")
      (node (ref "PIN22") (pin "1") (pinfunction "P_1") (pintype "passive"))
      (node (ref "U$1") (pin "22/A8") (pinfunction "22/A8_22/A8") (pintype "bidirectional"))
    )
    (net (code "51") (name "Net-(PIN23-P)") (class "Default")
      (node (ref "PIN23") (pin "1") (pinfunction "P_1") (pintype "passive"))
      (node (ref "R25") (pin "2") (pinfunction "2_2") (pintype "passive"))
      (node (ref "U$1") (pin "23/A9") (pinfunction "23/A9_23/A9") (pintype "bidirectional"))
    )
    (net (code "52") (name "Net-(RSA4-P)") (class "Default")
      (node (ref "D10") (pin "A") (pinfunction "A_A") (pintype "passive"))
      (node (ref "D11") (pin "A") (pinfunction "A_A") (pintype "passive"))
      (node (ref "RSA4") (pin "1") (pinfunction "P_1") (pintype "passive"))
    )
    (net (code "53") (name "Net-(RSA6-P)") (class "Default")
      (node (ref "D12") (pin "A") (pinfunction "A_A") (pintype "passive"))
      (node (ref "D13") (pin "A") (pinfunction "A_A") (pintype "passive"))
      (node (ref "RSA6") (pin "1") (pinfunction "P_1") (pintype "passive"))
    )
    (net (code "54") (name "Net-(RSA7-P)") (class "Default")
      (node (ref "D14") (pin "A") (pinfunction "A_A") (pintype "passive"))
      (node (ref "D15") (pin "A") (pinfunction "A_A") (pintype "passive"))
      (node (ref "RSA7") (pin "1") (pinfunction "P_1") (pintype "passive"))
    )
    (net (code "55") (name "Net-(RSA8-P)") (class "Default")
      (node (ref "D16") (pin "A") (pinfunction "A_A") (pintype "passive"))
      (node (ref "D17") (pin "A") (pinfunction "A_A") (pintype "passive"))
      (node (ref "D18") (pin "A") (pinfunction "A_A") (pintype "passive"))
      (node (ref "RSA8") (pin "1") (pinfunction "P_1") (pintype "passive"))
    )
    (net (code "56") (name "Net-(RSB4-P)") (class "Default")
      (node (ref "D2") (pin "A") (pinfunction "A_A") (pintype "passive"))
      (node (ref "D3") (pin "A") (pinfunction "A_A") (pintype "passive"))
      (node (ref "RSB4") (pin "1") (pinfunction "P_1") (pintype "passive"))
    )
    (net (code "57") (name "Net-(RSB6-P)") (class "Default")
      (node (ref "D4") (pin "A") (pinfunction "A_A") (pintype "passive"))
      (node (ref "D6") (pin "A") (pinfunction "A_A") (pintype "passive"))
      (node (ref "RSB6") (pin "1") (pinfunction "P_1") (pintype "passive"))
    )
    (net (code "58") (name "Net-(RSB7-P)") (class "Default")
      (node (ref "D7") (pin "A") (pinfunction "A_A") (pintype "passive"))
      (node (ref "D8") (pin "A") (pinfunction "A_A") (pintype "passive"))
      (node (ref "RSB7") (pin "1") (pinfunction "P_1") (pintype "passive"))
    )
    (net (code "59") (name "Net-(RSB8-P)") (class "Default")
      (node (ref "D19") (pin "A") (pinfunction "A_A") (pintype "passive"))
      (node (ref "D20") (pin "A") (pinfunction "A_A") (pintype "passive"))
      (node (ref "D9") (pin "A") (pinfunction "A_A") (pintype "passive"))
      (node (ref "RSB8") (pin "1") (pinfunction "P_1") (pintype "passive"))
    )
    (net (code "60") (name "Net-(U$2-VINA+)") (class "Default")
      (node (ref "R2") (pin "1") (pinfunction "1_1") (pintype "passive"))
      (node (ref "R3") (pin "2") (pinfunction "2_2") (pintype "passive"))
      (node (ref "U$2") (pin "3") (pinfunction "VINA+_3") (pintype "input"))
    )
    (net (code "61") (name "Net-(U$2-VINA-)") (class "Default")
      (node (ref "C66") (pin "2") (pinfunction "2_2") (pintype "passive"))
      (node (ref "R29") (pin "2") (pinfunction "2_2") (pintype "passive"))
      (node (ref "R6") (pin "1") (pinfunction "1_1") (pintype "passive"))
      (node (ref "U$2") (pin "2") (pinfunction "VINA-_2") (pintype "input"))
    )
    (net (code "62") (name "Net-(U$2-VINB+)") (class "Default")
      (node (ref "R1") (pin "2") (pinfunction "2_2") (pintype "passive"))
      (node (ref "R27") (pin "1") (pinfunction "1_1") (pintype "passive"))
      (node (ref "U$2") (pin "5") (pinfunction "VINB+_5") (pintype "input"))
    )
    (net (code "63") (name "Net-(U$2-VINB-)") (class "Default")
      (node (ref "C3") (pin "2") (pinfunction "2_2") (pintype "passive"))
      (node (ref "R4") (pin "2") (pinfunction "2_2") (pintype "passive"))
      (node (ref "R5") (pin "1") (pinfunction "1_1") (pintype "passive"))
      (node (ref "U$2") (pin "6") (pinfunction "VINB-_6") (pintype "input"))
    )
    (net (code "64") (name "Net-(U$2-VOUTA)") (class "Default")
      (node (ref "C12") (pin "1") (pinfunction "1_1") (pintype "passive"))
      (node (ref "C66") (pin "1") (pinfunction "1_1") (pintype "passive"))
      (node (ref "R29") (pin "1") (pinfunction "1_1") (pintype "passive"))
      (node (ref "U$2") (pin "1") (pinfunction "VOUTA_1") (pintype "output"))
    )
    (net (code "65") (name "Net-(U$2-VOUTB)") (class "Default")
      (node (ref "C13") (pin "1") (pinfunction "1_1") (pintype "passive"))
      (node (ref "C3") (pin "1") (pinfunction "1_1") (pintype "passive"))
      (node (ref "R4") (pin "1") (pinfunction "1_1") (pintype "passive"))
      (node (ref "U$2") (pin "7") (pinfunction "VOUTB_7") (pintype "output"))
    )
    (net (code "66") (name "Net-(VIN-P)") (class "Default")
      (node (ref "C1") (pin "+") (pinfunction "+_+") (pintype "passive"))
      (node (ref "C14") (pin "2") (pinfunction "2_2") (pintype "passive"))
      (node (ref "VIN") (pin "1") (pinfunction "P_1") (pintype "passive"))
      (node (ref "XL1") (pin "VIN") (pinfunction "VIN_VIN") (pintype "bidirectional"))
    )
    (net (code "67") (name "PE") (class "Default")
      (node (ref "C1") (pin "-") (pinfunction "-_-") (pintype "passive"))
      (node (ref "C10") (pin "2") (pinfunction "2_2") (pintype "passive"))
      (node (ref "C11") (pin "2") (pinfunction "2_2") (pintype "passive"))
      (node (ref "C14") (pin "1") (pinfunction "1_1") (pintype "passive"))
      (node (ref "C2") (pin "-") (pinfunction "-_-") (pintype "passive"))
      (node (ref "C30") (pin "1") (pinfunction "1_1") (pintype "passive"))
      (node (ref "C49") (pin "1") (pinfunction "1_1") (pintype "passive"))
      (node (ref "C51") (pin "2") (pinfunction "2_2") (pintype "passive"))
      (node (ref "C52") (pin "1") (pinfunction "1_1") (pintype "passive"))
      (node (ref "C53") (pin "2") (pinfunction "2_2") (pintype "passive"))
      (node (ref "C59") (pin "1") (pinfunction "1_1") (pintype "passive"))
      (node (ref "C63") (pin "2") (pinfunction "2_2") (pintype "passive"))
      (node (ref "C64") (pin "2") (pinfunction "2_2") (pintype "passive"))
      (node (ref "C68") (pin "2") (pinfunction "2_2") (pintype "passive"))
      (node (ref "D1") (pin "A") (pinfunction "A_A") (pintype "passive"))
      (node (ref "FS-1") (pin "1") (pinfunction "P_1") (pintype "passive"))
      (node (ref "FS-2") (pin "1") (pinfunction "P_1") (pintype "passive"))
      (node (ref "GND") (pin "1") (pinfunction "P_1") (pintype "passive"))
      (node (ref "GND10") (pin "1") (pinfunction "P_1") (pintype "passive"))
      (node (ref "IC2") (pin "11") (pinfunction "HPGND_11") (pintype "bidirectional"))
      (node (ref "IC2") (pin "15") (pinfunction "AGND_15") (pintype "bidirectional"))
      (node (ref "IC2") (pin "21") (pinfunction "MODE_21") (pintype "bidirectional"))
      (node (ref "IC2") (pin "22") (pinfunction "CSB_22") (pintype "bidirectional"))
      (node (ref "IC2") (pin "28") (pinfunction "DGND_28") (pintype "bidirectional"))
      (node (ref "IC5") (pin "5") (pinfunction "VL_5") (pintype "power_in"))
      (node (ref "J1") (pin "SLEEVE") (pinfunction "SL-CONT_SLEEVE") (pintype "bidirectional"))
      (node (ref "J1") (pin "SLEEVE-NORMAL") (pinfunction "SLVE-NORM_SLEEVE-NORMAL") (pintype "bidirectional"))
      (node (ref "J2") (pin "SLEEVE") (pinfunction "SL-CONT_SLEEVE") (pintype "bidirectional"))
      (node (ref "J2") (pin "SLEEVE-NORMAL") (pinfunction "SLVE-NORM_SLEEVE-NORMAL") (pintype "bidirectional"))
      (node (ref "J3") (pin "SLEEVE") (pinfunction "SL-CONT_SLEEVE") (pintype "bidirectional"))
      (node (ref "J3") (pin "SLEEVE-NORMAL") (pinfunction "SLVE-NORM_SLEEVE-NORMAL") (pintype "bidirectional"))
      (node (ref "J4") (pin "SLEEVE") (pinfunction "SL-CONT_SLEEVE") (pintype "bidirectional"))
      (node (ref "J4") (pin "SLEEVE-NORMAL") (pinfunction "SLVE-NORM_SLEEVE-NORMAL") (pintype "bidirectional"))
      (node (ref "LED-1") (pin "1") (pinfunction "P_1") (pintype "passive"))
      (node (ref "LED-2") (pin "1") (pinfunction "P_1") (pintype "passive"))
      (node (ref "M02") (pin "1") (pinfunction "P_1") (pintype "passive"))
      (node (ref "PIN25") (pin "1") (pinfunction "P_1") (pintype "passive"))
      (node (ref "R13") (pin "1") (pinfunction "1_1") (pintype "passive"))
      (node (ref "R15") (pin "1") (pinfunction "1_1") (pintype "passive"))
      (node (ref "R2") (pin "2") (pinfunction "2_2") (pintype "passive"))
      (node (ref "R27") (pin "2") (pinfunction "2_2") (pintype "passive"))
      (node (ref "R30") (pin "2") (pinfunction "2_2") (pintype "passive"))
      (node (ref "R31") (pin "2") (pinfunction "2_2") (pintype "passive"))
      (node (ref "R32") (pin "2") (pinfunction "2_2") (pintype "passive"))
      (node (ref "R33") (pin "2") (pinfunction "2_2") (pintype "passive"))
      (node (ref "R34") (pin "2") (pinfunction "2_2") (pintype "passive"))
      (node (ref "R35") (pin "2") (pinfunction "2_2") (pintype "passive"))
      (node (ref "U$1") (pin "GND") (pinfunction "GND_GND") (pintype "bidirectional"))
      (node (ref "U$1") (pin "GND2") (pinfunction "GND2_GND2") (pintype "bidirectional"))
      (node (ref "U$2") (pin "4") (pinfunction "VSS_4") (pintype "power_in"))
      (node (ref "U1") (pin "1") (pinfunction "ADJ/GND_1") (pintype "power_in"))
      (node (ref "XL1") (pin "GND") (pinfunction "GND_GND") (pintype "bidirectional"))
      (node (ref "XL1") (pin "GND1") (pinfunction "GND1_GND1") (pintype "bidirectional"))
      (node (ref "XL1") (pin "GND2") (pinfunction "GND2_GND2") (pintype "bidirectional"))
      (node (ref "XL1") (pin "GND3") (pinfunction "GND3_GND3") (pintype "bidirectional"))
      (node (ref "XL1") (pin "ONOFF") (pinfunction "ONOFF_ONOFF") (pintype "bidirectional"))
    )
    (net (code "68") (name "unconnected-(IC2-CLKOUT-Pad2)") (class "Default")
      (node (ref "IC2") (pin "2") (pinfunction "CLKOUT_2") (pintype "bidirectional"))
    )
    (net (code "69") (name "unconnected-(IC2-LHPOUT-Pad9)") (class "Default")
      (node (ref "IC2") (pin "9") (pinfunction "LHPOUT_9") (pintype "bidirectional"))
    )
    (net (code "70") (name "unconnected-(IC2-MICBIAS-Pad17)") (class "Default")
      (node (ref "IC2") (pin "17") (pinfunction "MICBIAS_17") (pintype "bidirectional"))
    )
    (net (code "71") (name "unconnected-(IC2-MICIN-Pad18)") (class "Default")
      (node (ref "IC2") (pin "18") (pinfunction "MICIN_18") (pintype "bidirectional"))
    )
    (net (code "72") (name "unconnected-(IC2-RHPOUT-Pad10)") (class "Default")
      (node (ref "IC2") (pin "10") (pinfunction "RHPOUT_10") (pintype "bidirectional"))
    )
    (net (code "73") (name "unconnected-(IC2-XTO-Pad26)") (class "Default")
      (node (ref "IC2") (pin "26") (pinfunction "XTO_26") (pintype "bidirectional"))
    )
    (net (code "74") (name "unconnected-(IC5-D-Pad1)") (class "Default")
      (node (ref "IC5") (pin "1") (pinfunction "D_1") (pintype "bidirectional"))
    )
    (net (code "75") (name "unconnected-(J1-TIP-CONT-PadTIP)") (class "Default")
      (node (ref "J1") (pin "TIP") (pinfunction "TIP-CONT_TIP") (pintype "bidirectional"))
    )
    (net (code "76") (name "unconnected-(J3-TIP-CONT-PadTIP)") (class "Default")
      (node (ref "J3") (pin "TIP") (pinfunction "TIP-CONT_TIP") (pintype "bidirectional"))
    )
    (net (code "77") (name "unconnected-(J4-TIP-CONT-PadTIP)") (class "Default")
      (node (ref "J4") (pin "TIP") (pinfunction "TIP-CONT_TIP") (pintype "bidirectional"))
    )
    (net (code "78") (name "unconnected-(RSA1-P-Pad1)") (class "Default")
      (node (ref "RSA1") (pin "1") (pinfunction "P_1") (pintype "passive"))
    )
    (net (code "79") (name "unconnected-(RSB1-P-Pad1)") (class "Default")
      (node (ref "RSB1") (pin "1") (pinfunction "P_1") (pintype "passive"))
    )
    (net (code "80") (name "unconnected-(U$1-Pad3V3_LN)") (class "Default")
      (node (ref "U$1") (pin "3V3_LN") (pinfunction "3V3_LN_3V3_LN") (pintype "bidirectional"))
    )
    (net (code "81") (name "unconnected-(U$1-PadGND3)") (class "Default")
      (node (ref "U$1") (pin "GND3") (pinfunction "GND3_GND3") (pintype "bidirectional"))
    )
    (net (code "82") (name "unconnected-(U$1-PadON{slash}OFF)") (class "Default")
      (node (ref "U$1") (pin "ON/OFF") (pinfunction "ON/OFF_ON/OFF") (pintype "bidirectional"))
    )
    (net (code "83") (name "unconnected-(U$1-PadPROG)") (class "Default")
      (node (ref "U$1") (pin "PROG") (pinfunction "PROG_PROG") (pintype "bidirectional"))
    )
    (net (code "84") (name "unconnected-(U$1-VBAT-PadVBAT\\)") (class "Default")
      (node (ref "U$1") (pin "VBAT\\") (pinfunction "VBAT_VBAT\\") (pintype "bidirectional"))
    )
  )
)
